# Charging_IC.net
KiCad netlist of a schematic drawn in Altium Designer
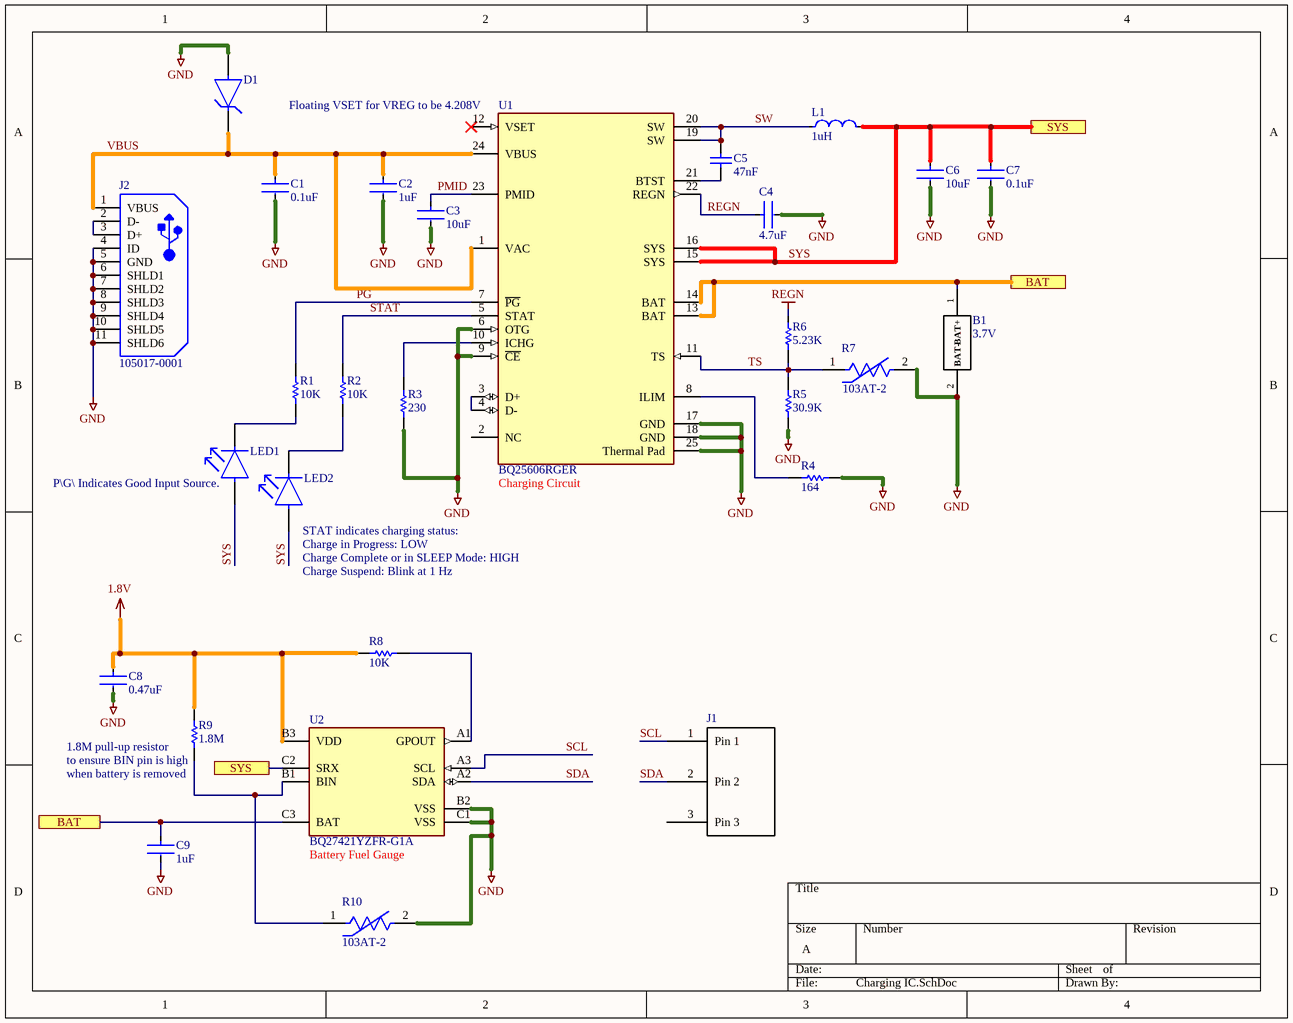
[diagram p0: Charging IC.SchDoc]

(export (version "E")
  (design (tool "Eeschema 10.0.6"))
  (components
    (comp (ref "B1") (value "3.7V") (libsource (lib "3.7V Li-Ion Battery") (part "B1")))
    (comp (ref "C1")
      (value "0.1uF")
      (footprint "FP-CC0603-DA-MFG")
      (description "CAP CER 0.1UF 16V X7R 0603")
      (fields
        (field (name "OCTOPART") "https://octopart.com/cc0603krx7r7bb104-yageo-192941")
        (field (name "TOLERANCE") "0.1")
      )
      (libsource (lib "Altium Content Vault") (part "11868f565c42a9108669ba33697ecf6"))
    )
    (comp (ref "C2")
      (value "1uF")
      (footprint "FP-0603-L_1_6_0_15-W_0_8-IPC_C")
      (description "Ceramic Capacitor General Use 1uF ±10% 50V X7R 0603")
      (fields (field (name "TOLERANCE") "10%"))
      (libsource (lib "Altium Content Vault") (part "11868f565c42a9108669ba33697ecf6"))
    )
    (comp (ref "C3")
      (value "10uF")
      (footprint "FP-GRM188-0_1-e0_2_0_55-IPC_A")
      (description "Chip Multilayer Ceramic Capacitors for General Purpose, 0603, 10uF, X5R, 15%, 20%, 6.3V")
      (fields (field (name "VOLTAGE") "6.3V") (field (name "TOLERANCE") "20%"))
      (libsource (lib "Altium Content Vault") (part "02cd4be3c70576c341d710602a673aa"))
    )
    (comp (ref "C4")
      (value "4.7uF")
      (footprint "FP-C0603-CG-MFG")
      (description "CAP CER 4.7UF 6.3V X5R 0603")
      (fields (field (name "TOLERANCE") "10%") (field (name "MANUFACTURER") "Kemet"))
      (libsource (lib "Altium Content Vault") (part "11868f565c42a9108669ba33697ecf6"))
    )
    (comp (ref "C5")
      (value "47nF")
      (footprint "CAPC1608X90X35ML10T15")
      (fields (field (name "MANUFACTURER") "Murata") (field (name "PART NUMBER") "GRM188R71H473KA61D"))
      (libsource (lib "Altium Content Vault") (part "CAP"))
    )
    (comp (ref "C6")
      (value "10uF")
      (footprint "FP-GRM188-0_1-e0_2_0_55-IPC_A")
      (description "Chip Multilayer Ceramic Capacitors for General Purpose, 0603, 10uF, X5R, 15%, 20%, 6.3V")
      (fields (field (name "VOLTAGE") "6.3V") (field (name "TOLERANCE") "20%"))
      (libsource (lib "Altium Content Vault") (part "02cd4be3c70576c341d710602a673aa"))
    )
    (comp (ref "C7")
      (value "0.1uF")
      (footprint "FP-CC0603-DA-MFG")
      (description "CAP CER 0.1UF 16V X7R 0603")
      (fields
        (field (name "OCTOPART") "https://octopart.com/cc0603krx7r7bb104-yageo-192941")
        (field (name "TOLERANCE") "0.1")
      )
      (libsource (lib "Altium Content Vault") (part "11868f565c42a9108669ba33697ecf6"))
    )
    (comp (ref "C8")
      (value "0.47uF")
      (footprint "FP-0603-L_1_6_0_1-W_0_8_0-IPC_B")
      (description "None")
      (fields (field (name "TOLERANCE") "10%") (field (name "VOLTAGE") "50V"))
      (libsource (lib "Altium Content Vault") (part "02cd4be3c70576c341d710602a673aa"))
    )
    (comp (ref "C9")
      (value "1uF")
      (footprint "FP-0603-L_1_6_0_15-W_0_8-IPC_C")
      (description "Ceramic Capacitor General Use 1uF ±10% 50V X7R 0603")
      (fields (field (name "TOLERANCE") "10%"))
      (libsource (lib "Altium Content Vault") (part "11868f565c42a9108669ba33697ecf6"))
    )
    (comp (ref "D1")
      (value "CZRU52C3V3")
      (footprint "FP-0603-SOD-523F-MFG")
      (description "DIODE ZENER 3.3V 150MW 0603")
      (fields (field (name "TOLERANCE") "5%"))
      (libsource (lib "Altium Content Vault") (part "f813f71cba58e380607f5dd3caf9714"))
    )
    (comp (ref "J1") (value "~") (libsource (lib "Schlib1") (part "Component_1")))
    (comp (ref "J2")
      (value "105017-0001")
      (footprint "USB-MICRO-B_V")
      (fields (field (name "MANUFACTURER") "Molex"))
      (libsource (lib "Altium Content Vault") (part "USB-5-6SHLD"))
    )
    (comp (ref "L1")
      (value "1uH")
      (footprint "FP-MLZ1608-MFG")
      (description "FIXED IND 1UH 600MA 150 MOHM SMD")
      (fields (field (name "TOLERANCE") "20%"))
      (libsource (lib "Altium Content Vault") (part "725321dda6339637d4d059423bc1c3c"))
    )
    (comp (ref "LED1")
      (value "LTST-C190GKT")
      (footprint "FP-LTST-C190GKT-MFG")
      (description "LED GREEN CLEAR CHIP SMD")
      (fields (field (name "VOLTAGE") "2V"))
      (libsource (lib "Altium Content Vault") (part "8706943c75ba83719d021d2fdc84c58"))
    )
    (comp (ref "LED2")
      (value "LTST-C190GKT")
      (footprint "FP-LTST-C190GKT-MFG")
      (description "LED GREEN CLEAR CHIP SMD")
      (fields (field (name "VOLTAGE") "2V"))
      (libsource (lib "Altium Content Vault") (part "8706943c75ba83719d021d2fdc84c58"))
    )
    (comp (ref "R1")
      (value "10K")
      (footprint "RESC1609X50X30NL8T20")
      (description "Chip Resistor, 10 KOhm, +/- 1%, 100 mW, -55 to 155 degC, 0603 (1608 Metric), RoHS, Tape and Reel")
      (fields (field (name "MANUFACTURER") "Vishay Semiconductor"))
      (libsource (lib "Altium Content Vault") (part "RES-2"))
    )
    (comp (ref "R2")
      (value "10K")
      (footprint "RESC1609X50X30NL8T20")
      (description "Chip Resistor, 10 KOhm, +/- 1%, 100 mW, -55 to 155 degC, 0603 (1608 Metric), RoHS, Tape and Reel")
      (fields (field (name "MANUFACTURER") "Vishay Semiconductor"))
      (libsource (lib "Altium Content Vault") (part "RES-2"))
    )
    (comp (ref "R3")
      (value "230")
      (footprint "RESC1609X50X30ML8T20")
      (description "Chip Resistor, 100 Ohm, +/- 1%, 100 mW,-55 to 155 degC, 0603 (1608 Metric), RoHS, Tape and Ree")
      (fields (field (name "MANUFACTURER") "Vishay Semiconductor"))
      (libsource (lib "Altium Content Vault") (part "RES-2"))
    )
    (comp (ref "R4")
      (value "164")
      (footprint "RESC1609X50X30ML8T20")
      (description "Chip Resistor, 100 Ohm, +/- 1%, 100 mW,-55 to 155 degC, 0603 (1608 Metric), RoHS, Tape and Ree")
      (fields (field (name "MANUFACTURER") "Vishay Semiconductor"))
      (libsource (lib "Altium Content Vault") (part "RES-2"))
    )
    (comp (ref "R5")
      (value "30.9K")
      (footprint "RESC1608X55X30ML15T15")
      (fields (field (name "MANUFACTURER") "Panasonic") (field (name "PART NUMBER") "ERJ-3EKF3092V"))
      (libsource (lib "Altium Content Vault") (part "RES"))
    )
    (comp (ref "R6")
      (value "5.23K")
      (footprint "RESC1608X55X30NL15T15")
      (fields (field (name "MANUFACTURER") "Panasonic") (field (name "PART NUMBER") "ERJ-3EKF5231V"))
      (libsource (lib "Altium Content Vault") (part "RES"))
    )
    (comp (ref "R7")
      (value "103AT-2")
      (footprint "FP-103AT-2-MFG")
      (description "Thermistor NTC 10KOhm 1% 2-Pin")
      (fields (field (name "TOLERANCE") "1%"))
      (libsource (lib "Altium Content Vault") (part "3b148a6ebabc5fb4d708a66c052d352"))
    )
    (comp (ref "R8")
      (value "10K")
      (footprint "RESC1609X50X30NL8T20")
      (description "Chip Resistor, 10 KOhm, +/- 1%, 100 mW, -55 to 155 degC, 0603 (1608 Metric), RoHS, Tape and Reel")
      (fields (field (name "MANUFACTURER") "Vishay Semiconductor"))
      (libsource (lib "Altium Content Vault") (part "RES-2"))
    )
    (comp (ref "R9")
      (value "1.8M")
      (footprint "RESC1609X50X30LL10T20")
      (fields (field (name "PART NUMBER") "CRCW06031M80JNEA") (field (name "MANUFACTURER") "Vishay Dale"))
      (libsource (lib "Altium Content Vault") (part "RES"))
    )
    (comp (ref "R10")
      (value "103AT-2")
      (footprint "FP-103AT-2-MFG")
      (description "Thermistor NTC 10KOhm 1% 2-Pin")
      (fields (field (name "TOLERANCE") "1%"))
      (libsource (lib "Altium Content Vault") (part "3b148a6ebabc5fb4d708a66c052d352"))
    )
    (comp (ref "U1")
      (value "BQ25606RGER")
      (footprint "FP-RGE0024H-IPC_C")
      (description "IC BATT CHG LI-ION 1 CELL 24VQFN")
      (libsource (lib "Altium Content Vault") (part "ea5adc10b52c51cd7be3fcfecdf6045"))
    )
    (comp (ref "U2")
      (value "BQ27421YZFR-G1A")
      (footprint "FP-YZF0009-C01-MFG")
      (description "IC BATT FUEL GAUGE LICO2 9DSBGA")
      (libsource (lib "Altium Content Vault") (part "4c6ed9f2c1574ff3451f58014736652"))
    )
  )
  (nets
    (net (code "1") (name "/BAT") (class "Default")
      (node (ref "B1") (pin "1") (pinfunction "BAT+_1") (pintype "passive"))
      (node (ref "C9") (pin "1") (pinfunction "1_1") (pintype "passive"))
      (node (ref "U1") (pin "13") (pinfunction "BAT_13") (pintype "power_in"))
      (node (ref "U1") (pin "14") (pinfunction "BAT_14") (pintype "power_in"))
      (node (ref "U2") (pin "C3") (pinfunction "BAT_C3") (pintype "power_in"))
    )
    (net (code "2") (name "/PG") (class "Default")
      (node (ref "R1") (pin "2") (pinfunction "2_2") (pintype "passive"))
      (node (ref "U1") (pin "7") (pinfunction "~{PG}_7") (pintype "open_collector"))
    )
    (net (code "3") (name "/PMID") (class "Default")
      (node (ref "C3") (pin "1") (pinfunction "1_1") (pintype "passive"))
      (node (ref "U1") (pin "23") (pinfunction "PMID_23") (pintype "passive"))
    )
    (net (code "4") (name "/SCL") (class "Default")
      (node (ref "J1") (pin "1") (pinfunction "Pin_1_1") (pintype "passive"))
      (node (ref "U2") (pin "A3") (pinfunction "SCL_A3") (pintype "input"))
    )
    (net (code "5") (name "/SDA") (class "Default")
      (node (ref "J1") (pin "2") (pinfunction "Pin_2_2") (pintype "passive"))
      (node (ref "U2") (pin "A2") (pinfunction "SDA_A2") (pintype "bidirectional"))
    )
    (net (code "6") (name "/STAT") (class "Default")
      (node (ref "R2") (pin "2") (pinfunction "2_2") (pintype "passive"))
      (node (ref "U1") (pin "5") (pinfunction "STAT_5") (pintype "open_collector"))
    )
    (net (code "7") (name "/SW") (class "Default")
      (node (ref "C5") (pin "2") (pinfunction "2_2") (pintype "passive"))
      (node (ref "L1") (pin "1") (pinfunction "1_1") (pintype "passive"))
      (node (ref "U1") (pin "19") (pinfunction "SW_19") (pintype "power_in"))
      (node (ref "U1") (pin "20") (pinfunction "SW_20") (pintype "power_in"))
    )
    (net (code "8") (name "/SYS") (class "Default")
      (node (ref "C6") (pin "1") (pinfunction "1_1") (pintype "passive"))
      (node (ref "C7") (pin "1") (pinfunction "1_1") (pintype "passive"))
      (node (ref "L1") (pin "2") (pinfunction "2_2") (pintype "passive"))
      (node (ref "LED1") (pin "2") (pinfunction "A_2") (pintype "passive"))
      (node (ref "LED2") (pin "2") (pinfunction "A_2") (pintype "passive"))
      (node (ref "U1") (pin "15") (pinfunction "SYS_15") (pintype "power_in"))
      (node (ref "U1") (pin "16") (pinfunction "SYS_16") (pintype "power_in"))
      (node (ref "U2") (pin "C2") (pinfunction "SRX_C2") (pintype "passive"))
    )
    (net (code "9") (name "/TS") (class "Default")
      (node (ref "R5") (pin "2") (pinfunction "2_2") (pintype "passive"))
      (node (ref "R6") (pin "1") (pinfunction "1_1") (pintype "passive"))
      (node (ref "R7") (pin "1") (pinfunction "1_1") (pintype "passive"))
      (node (ref "U1") (pin "11") (pinfunction "TS_11") (pintype "input"))
    )
    (net (code "10") (name "/VBUS") (class "Default")
      (node (ref "C1") (pin "1") (pinfunction "1_1") (pintype "passive"))
      (node (ref "C2") (pin "1") (pinfunction "1_1") (pintype "passive"))
      (node (ref "D1") (pin "1") (pinfunction "C_1") (pintype "passive"))
      (node (ref "J2") (pin "1") (pinfunction "VBUS_1") (pintype "passive"))
      (node (ref "U1") (pin "1") (pinfunction "VAC_1") (pintype "power_in"))
      (node (ref "U1") (pin "24") (pinfunction "VBUS_24") (pintype "power_in"))
    )
    (net (code "11") (name "1.8V") (class "Default")
      (node (ref "C8") (pin "1") (pinfunction "1_1") (pintype "passive"))
      (node (ref "R8") (pin "2") (pinfunction "2_2") (pintype "passive"))
      (node (ref "R9") (pin "2") (pinfunction "2_2") (pintype "passive"))
      (node (ref "U2") (pin "B3") (pinfunction "VDD_B3") (pintype "power_in"))
    )
    (net (code "12") (name "GND") (class "Default")
      (node (ref "B1") (pin "2") (pinfunction "BAT-_2") (pintype "passive"))
      (node (ref "C1") (pin "2") (pinfunction "2_2") (pintype "passive"))
      (node (ref "C2") (pin "2") (pinfunction "2_2") (pintype "passive"))
      (node (ref "C3") (pin "2") (pinfunction "2_2") (pintype "passive"))
      (node (ref "C4") (pin "2") (pinfunction "2_2") (pintype "passive"))
      (node (ref "C6") (pin "2") (pinfunction "2_2") (pintype "passive"))
      (node (ref "C7") (pin "2") (pinfunction "2_2") (pintype "passive"))
      (node (ref "C8") (pin "2") (pinfunction "2_2") (pintype "passive"))
      (node (ref "C9") (pin "2") (pinfunction "2_2") (pintype "passive"))
      (node (ref "D1") (pin "2") (pinfunction "A_2") (pintype "passive"))
      (node (ref "J2") (pin "10") (pinfunction "SHLD5_10") (pintype "passive"))
      (node (ref "J2") (pin "11") (pinfunction "SHLD6_11") (pintype "passive"))
      (node (ref "J2") (pin "4") (pinfunction "ID_4") (pintype "passive"))
      (node (ref "J2") (pin "5") (pinfunction "GND_5") (pintype "passive"))
      (node (ref "J2") (pin "6") (pinfunction "SHLD1_6") (pintype "passive"))
      (node (ref "J2") (pin "7") (pinfunction "SHLD2_7") (pintype "passive"))
      (node (ref "J2") (pin "8") (pinfunction "SHLD3_8") (pintype "passive"))
      (node (ref "J2") (pin "9") (pinfunction "SHLD4_9") (pintype "passive"))
      (node (ref "R10") (pin "2") (pinfunction "2_2") (pintype "passive"))
      (node (ref "R3") (pin "2") (pinfunction "2_2") (pintype "passive"))
      (node (ref "R4") (pin "2") (pinfunction "2_2") (pintype "passive"))
      (node (ref "R5") (pin "1") (pinfunction "1_1") (pintype "passive"))
      (node (ref "R7") (pin "2") (pinfunction "2_2") (pintype "passive"))
      (node (ref "U1") (pin "17") (pinfunction "GND_17") (pintype "power_in"))
      (node (ref "U1") (pin "18") (pinfunction "GND_18") (pintype "power_in"))
      (node (ref "U1") (pin "25") (pinfunction "Thermal_Pad_25") (pintype "power_in"))
      (node (ref "U1") (pin "6") (pinfunction "OTG_6") (pintype "input"))
      (node (ref "U1") (pin "9") (pinfunction "~{CE}_9") (pintype "input"))
      (node (ref "U2") (pin "B2") (pinfunction "VSS_B2") (pintype "power_in"))
      (node (ref "U2") (pin "C1") (pinfunction "VSS_C1") (pintype "power_in"))
    )
    (net (code "13") (name "Net-(J2-D+)") (class "Default")
      (node (ref "J2") (pin "2") (pinfunction "D-_2") (pintype "passive"))
      (node (ref "J2") (pin "3") (pinfunction "D+_3") (pintype "passive"))
    )
    (net (code "14") (name "Net-(LED1-C)") (class "Default")
      (node (ref "LED1") (pin "1") (pinfunction "C_1") (pintype "passive"))
      (node (ref "R1") (pin "1") (pinfunction "1_1") (pintype "passive"))
    )
    (net (code "15") (name "Net-(LED2-C)") (class "Default")
      (node (ref "LED2") (pin "1") (pinfunction "C_1") (pintype "passive"))
      (node (ref "R2") (pin "1") (pinfunction "1_1") (pintype "passive"))
    )
    (net (code "16") (name "Net-(U1-BTST)") (class "Default")
      (node (ref "C5") (pin "1") (pinfunction "1_1") (pintype "passive"))
      (node (ref "U1") (pin "21") (pinfunction "BTST_21") (pintype "power_in"))
    )
    (net (code "17") (name "Net-(U1-D+)") (class "Default")
      (node (ref "U1") (pin "3") (pinfunction "D+_3") (pintype "bidirectional"))
      (node (ref "U1") (pin "4") (pinfunction "D-_4") (pintype "bidirectional"))
    )
    (net (code "18") (name "Net-(U1-ICHG)") (class "Default")
      (node (ref "R3") (pin "1") (pinfunction "1_1") (pintype "passive"))
      (node (ref "U1") (pin "10") (pinfunction "ICHG_10") (pintype "input"))
    )
    (net (code "19") (name "Net-(U1-ILIM)") (class "Default")
      (node (ref "R4") (pin "1") (pinfunction "1_1") (pintype "passive"))
      (node (ref "U1") (pin "8") (pinfunction "ILIM_8") (pintype "passive"))
    )
    (net (code "20") (name "Net-(U2-BIN)") (class "Default")
      (node (ref "R10") (pin "1") (pinfunction "1_1") (pintype "passive"))
      (node (ref "R9") (pin "1") (pinfunction "1_1") (pintype "passive"))
      (node (ref "U2") (pin "B1") (pinfunction "BIN_B1") (pintype "passive"))
    )
    (net (code "21") (name "Net-(U2-GPOUT)") (class "Default")
      (node (ref "R8") (pin "1") (pinfunction "1_1") (pintype "passive"))
      (node (ref "U2") (pin "A1") (pinfunction "GPOUT_A1") (pintype "output"))
    )
    (net (code "22") (name "REGN") (class "Default")
      (node (ref "C4") (pin "1") (pinfunction "1_1") (pintype "passive"))
      (node (ref "R6") (pin "2") (pinfunction "2_2") (pintype "passive"))
      (node (ref "U1") (pin "22") (pinfunction "REGN_22") (pintype "output"))
    )
    (net (code "23") (name "unconnected-(J1-Pin_3-Pad3)") (class "Default")
      (node (ref "J1") (pin "3") (pinfunction "Pin_3_3") (pintype "passive"))
    )
    (net (code "24") (name "unconnected-(U1-NC-Pad2)") (class "Default")
      (node (ref "U1") (pin "2") (pinfunction "NC_2") (pintype "passive"))
    )
    (net (code "25") (name "unconnected-(U1-VSET-Pad12)") (class "Default")
      (node (ref "U1") (pin "12") (pinfunction "VSET_12") (pintype "input+no_connect"))
    )
  )
)
